# 06-DETECT-ps2-blueretro.net
KiCad netlist of a schematic drawn in Altium Designer
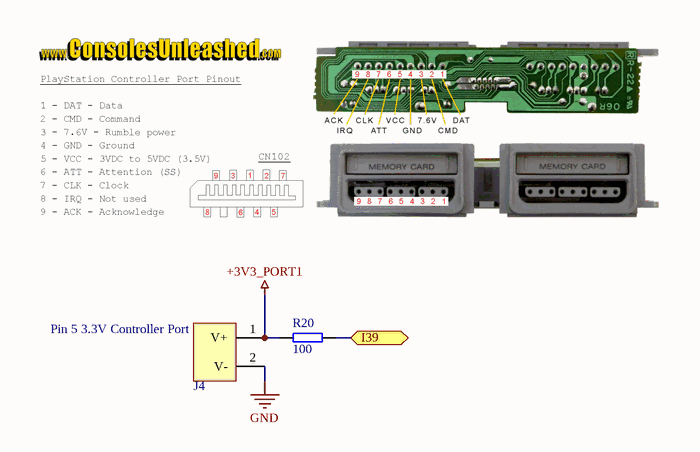
[diagram p0: 06-DETECT-ps2-blueretro.SchDoc]

(export (version "E")
  (design (tool "Eeschema 10.0.6"))
  (components
    (comp (ref "J4")
      (value "2 Pole 2.54mm")
      (footprint "2.54mm_2pole")
      (description "Solder contacts for a 2.54mm connector")
      (libsource (lib "mycomponents") (part "2 Pole 2.54mm"))
    )
    (comp (ref "R20")
      (value "100")
      (footprint "res_0603")
      (fields (field (name "Comment") "res_0603"))
      (libsource (lib "mycomponents") (part "res_0603"))
    )
  )
  (nets
    (net (code "1") (name "+3V3_PORT1") (class "Default")
      (node (ref "J4") (pin "1") (pinfunction "V+_1") (pintype "passive"))
      (node (ref "R20") (pin "2") (pinfunction "2_2") (pintype "passive"))
    )
    (net (code "2") (name "/I39") (class "Default")
      (node (ref "R20") (pin "1") (pinfunction "1_1") (pintype "passive"))
    )
    (net (code "3") (name "GND") (class "Default")
      (node (ref "J4") (pin "2") (pinfunction "V-_2") (pintype "passive"))
    )
  )
)
